# PAYL0004_PC_Microcontroller_IOIfaces.net
KiCad netlist of a schematic drawn in Altium Designer
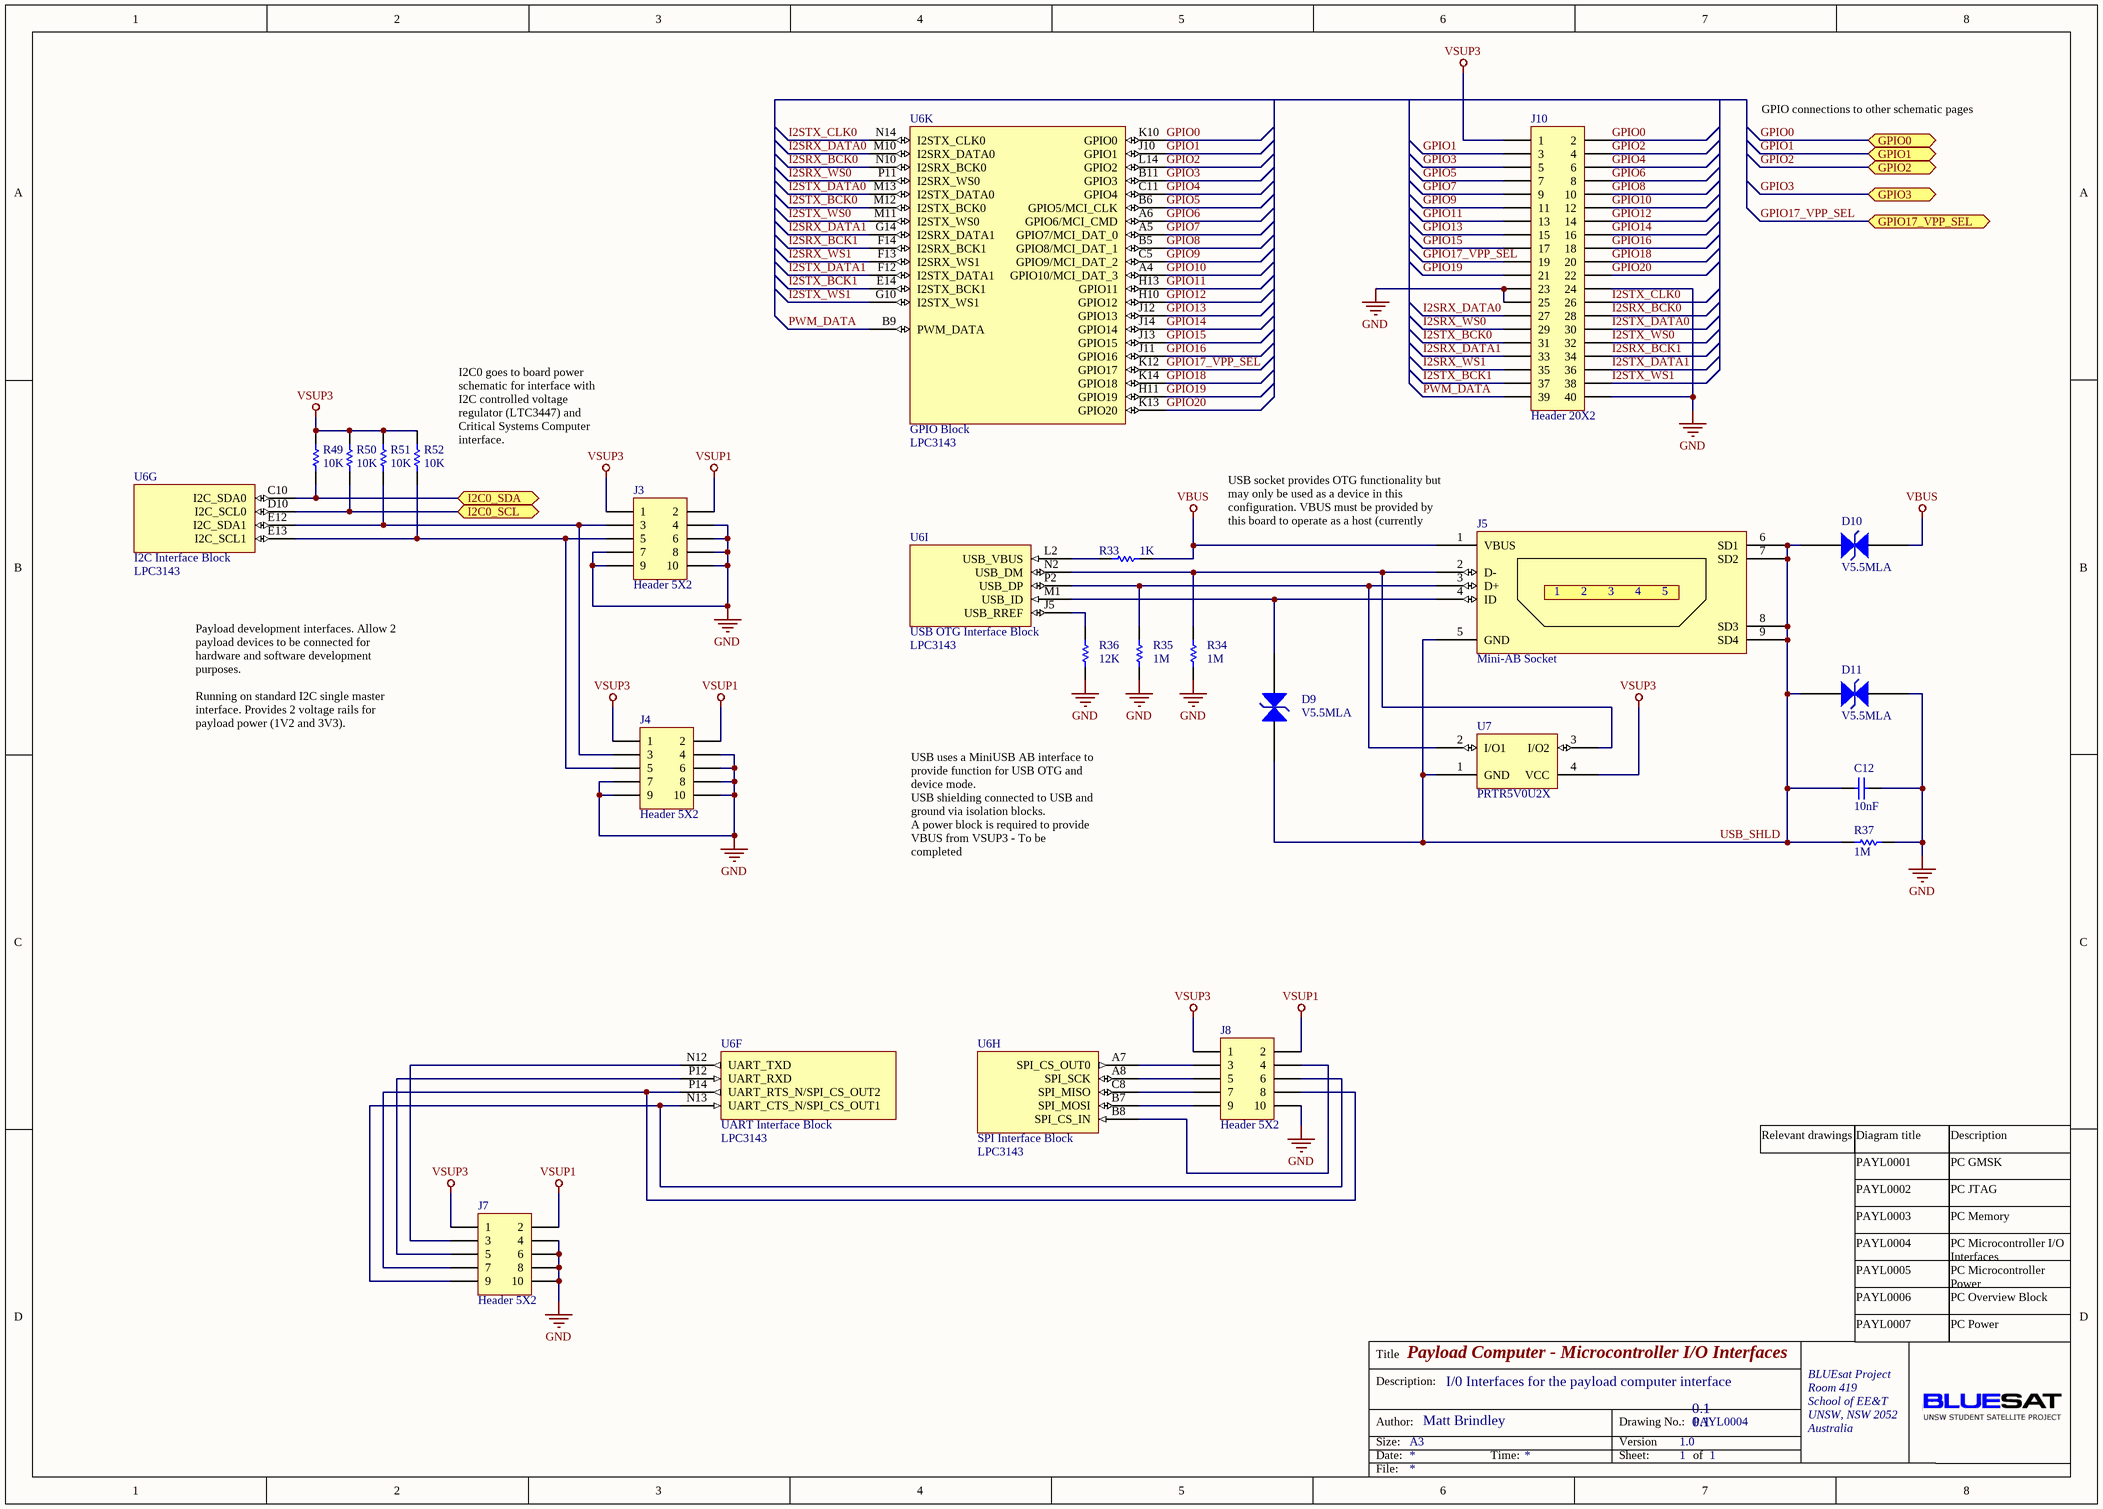
[diagram p0: PAYL0004_PC_Microcontroller_IOIfaces.SchDoc]

(export (version "E")
  (design (tool "Eeschema 10.0.6"))
  (components
    (comp (ref "C12")
      (value "10nF")
      (footprint "C0805")
      (description "Capacitor (Semiconductor SIM Model)")
      (fields (field (name "Comment") "Cap Semi") (field (name "PUBLISHER") "Altium Limited"))
      (libsource (lib "Miscellaneous Devices") (part "Cap Semi"))
    )
    (comp (ref "D9")
      (value "V5.5MLA")
      (footprint "MLA-1206")
      (description "Multilayer varistor - Transient voltage protection device")
      (fields (field (name "PUBLISHER") "Altium Limited"))
      (libsource (lib "PC_Components") (part "V5.5MLA0603"))
    )
    (comp (ref "D10")
      (value "V5.5MLA")
      (footprint "MLA-1206")
      (description "Multilayer varistor - Transient voltage protection device")
      (fields (field (name "PUBLISHER") "Altium Limited"))
      (libsource (lib "PC_Components") (part "V5.5MLA0603"))
    )
    (comp (ref "D11")
      (value "V5.5MLA")
      (footprint "MLA-1206")
      (description "Multilayer varistor - Transient voltage protection device")
      (fields (field (name "PUBLISHER") "Altium Limited"))
      (libsource (lib "PC_Components") (part "V5.5MLA0603"))
    )
    (comp (ref "J3")
      (value "Header 5X2")
      (footprint "HDR2X5")
      (description "Header, 5-Pin, Dual row")
      (fields (field (name "PUBLISHER") "Altium Limited"))
      (libsource (lib "Miscellaneous Connectors") (part "Header 5X2"))
    )
    (comp (ref "J4")
      (value "Header 5X2")
      (footprint "HDR2X5")
      (description "Header, 5-Pin, Dual row")
      (fields (field (name "PUBLISHER") "Altium Limited"))
      (libsource (lib "Miscellaneous Connectors") (part "Header 5X2"))
    )
    (comp (ref "J5")
      (value "Mini-AB Socket")
      (footprint "miniUSB-AB")
      (description "MiniUSB AB type socket")
      (fields (field (name "PUBLISHER") "Altium Limited"))
      (libsource (lib "PC_Components") (part "miniUSB-AB"))
    )
    (comp (ref "J7")
      (value "Header 5X2")
      (footprint "HDR2X5")
      (description "Header, 5-Pin, Dual row")
      (fields (field (name "PUBLISHER") "Altium Limited"))
      (libsource (lib "Miscellaneous Connectors") (part "Header 5X2"))
    )
    (comp (ref "J8")
      (value "Header 5X2")
      (footprint "HDR2X5")
      (description "Header, 5-Pin, Dual row")
      (fields (field (name "PUBLISHER") "Altium Limited"))
      (libsource (lib "Miscellaneous Connectors") (part "Header 5X2"))
    )
    (comp (ref "J10")
      (value "Header 20X2")
      (footprint "HDR2X20")
      (description "Header, 20-Pin, Dual row")
      (fields (field (name "PUBLISHER") "Altium Limited"))
      (libsource (lib "Miscellaneous Connectors") (part "Header 20X2"))
    )
    (comp (ref "R33")
      (value "1K")
      (footprint "6-0805_L")
      (description "Semiconductor Resistor")
      (fields (field (name "Comment") "Res Semi") (field (name "PUBLISHER") "Altium Limited"))
      (libsource (lib "Miscellaneous Devices") (part "Res Semi"))
    )
    (comp (ref "R34")
      (value "1M")
      (footprint "6-0805_L")
      (description "Semiconductor Resistor")
      (fields (field (name "Comment") "Res Semi") (field (name "PUBLISHER") "Altium Limited"))
      (libsource (lib "Miscellaneous Devices") (part "Res Semi"))
    )
    (comp (ref "R35")
      (value "1M")
      (footprint "6-0805_L")
      (description "Semiconductor Resistor")
      (fields (field (name "Comment") "Res Semi") (field (name "PUBLISHER") "Altium Limited"))
      (libsource (lib "Miscellaneous Devices") (part "Res Semi"))
    )
    (comp (ref "R36")
      (value "12K")
      (footprint "6-0805_L")
      (description "Semiconductor Resistor")
      (fields (field (name "Comment") "Res Semi") (field (name "PUBLISHER") "Altium Limited"))
      (libsource (lib "Miscellaneous Devices") (part "Res Semi"))
    )
    (comp (ref "R37")
      (value "1M")
      (footprint "6-0805_L")
      (description "Semiconductor Resistor")
      (fields (field (name "Comment") "Res Semi") (field (name "PUBLISHER") "Altium Limited"))
      (libsource (lib "Miscellaneous Devices") (part "Res Semi"))
    )
    (comp (ref "R49")
      (value "10K")
      (footprint "6-0805_L")
      (description "Semiconductor Resistor")
      (fields (field (name "Comment") "Res Semi") (field (name "PUBLISHER") "Altium Limited"))
      (libsource (lib "Miscellaneous Devices") (part "Res Semi"))
    )
    (comp (ref "R50")
      (value "10K")
      (footprint "6-0805_L")
      (description "Semiconductor Resistor")
      (fields (field (name "Comment") "Res Semi") (field (name "PUBLISHER") "Altium Limited"))
      (libsource (lib "Miscellaneous Devices") (part "Res Semi"))
    )
    (comp (ref "R51")
      (value "10K")
      (footprint "6-0805_L")
      (description "Semiconductor Resistor")
      (fields (field (name "Comment") "Res Semi") (field (name "PUBLISHER") "Altium Limited"))
      (libsource (lib "Miscellaneous Devices") (part "Res Semi"))
    )
    (comp (ref "R52")
      (value "10K")
      (footprint "6-0805_L")
      (description "Semiconductor Resistor")
      (fields (field (name "Comment") "Res Semi") (field (name "PUBLISHER") "Altium Limited"))
      (libsource (lib "Miscellaneous Devices") (part "Res Semi"))
    )
    (comp (ref "U6")
      (value "LPC3143")
      (footprint "PC_Footprints:BGA180C80P14X14_1200X1200X120")
      (description "NXP ARM9 based microcontroller")
      (fields (field (name "PUBLISHER") "BLUEsat Project"))
      (libsource (lib "PC_Components") (part "LPC3143"))
    )
    (comp (ref "U7")
      (value "PRTR5V0U2X")
      (footprint "SOT190P230X110-4N")
      (description "Electrostatic discharge protection diode IC - NXP")
      (fields (field (name "PUBLISHER") "Altium Limited"))
      (libsource (lib "PC_Components") (part "PRTR5V0U2X"))
    )
  )
  (nets
    (net (code "1") (name "/GPIO0") (class "Default")
      (node (ref "J10") (pin "2") (pinfunction "2_2") (pintype "passive"))
      (node (ref "U6") (pin "K10") (pinfunction "GPIO0_K10") (pintype "bidirectional"))
    )
    (net (code "2") (name "/GPIO1") (class "Default")
      (node (ref "J10") (pin "3") (pinfunction "3_3") (pintype "passive"))
      (node (ref "U6") (pin "J10") (pinfunction "GPIO1_J10") (pintype "bidirectional"))
    )
    (net (code "3") (name "/GPIO2") (class "Default")
      (node (ref "J10") (pin "4") (pinfunction "4_4") (pintype "passive"))
      (node (ref "U6") (pin "L14") (pinfunction "GPIO2_L14") (pintype "bidirectional"))
    )
    (net (code "4") (name "/GPIO3") (class "Default")
      (node (ref "J10") (pin "5") (pinfunction "5_5") (pintype "passive"))
      (node (ref "U6") (pin "B11") (pinfunction "GPIO3_B11") (pintype "bidirectional"))
    )
    (net (code "5") (name "/GPIO4") (class "Default")
      (node (ref "J10") (pin "6") (pinfunction "6_6") (pintype "passive"))
      (node (ref "U6") (pin "C11") (pinfunction "GPIO4_C11") (pintype "bidirectional"))
    )
    (net (code "6") (name "/GPIO5") (class "Default")
      (node (ref "J10") (pin "7") (pinfunction "7_7") (pintype "passive"))
      (node (ref "U6") (pin "B6") (pinfunction "GPIO5/MCI_CLK_B6") (pintype "bidirectional"))
    )
    (net (code "7") (name "/GPIO6") (class "Default")
      (node (ref "J10") (pin "8") (pinfunction "8_8") (pintype "passive"))
      (node (ref "U6") (pin "A6") (pinfunction "GPIO6/MCI_CMD_A6") (pintype "bidirectional"))
    )
    (net (code "8") (name "/GPIO7") (class "Default")
      (node (ref "J10") (pin "9") (pinfunction "9_9") (pintype "passive"))
      (node (ref "U6") (pin "A5") (pinfunction "GPIO7/MCI_DAT_0_A5") (pintype "bidirectional"))
    )
    (net (code "9") (name "/GPIO8") (class "Default")
      (node (ref "J10") (pin "10") (pinfunction "10_10") (pintype "passive"))
      (node (ref "U6") (pin "B5") (pinfunction "GPIO8/MCI_DAT_1_B5") (pintype "bidirectional"))
    )
    (net (code "10") (name "/GPIO9") (class "Default")
      (node (ref "J10") (pin "11") (pinfunction "11_11") (pintype "passive"))
      (node (ref "U6") (pin "C5") (pinfunction "GPIO9/MCI_DAT_2_C5") (pintype "bidirectional"))
    )
    (net (code "11") (name "/GPIO10") (class "Default")
      (node (ref "J10") (pin "12") (pinfunction "12_12") (pintype "passive"))
      (node (ref "U6") (pin "A4") (pinfunction "GPIO10/MCI_DAT_3_A4") (pintype "bidirectional"))
    )
    (net (code "12") (name "/GPIO11") (class "Default")
      (node (ref "J10") (pin "13") (pinfunction "13_13") (pintype "passive"))
      (node (ref "U6") (pin "H13") (pinfunction "GPIO11_H13") (pintype "bidirectional"))
    )
    (net (code "13") (name "/GPIO12") (class "Default")
      (node (ref "J10") (pin "14") (pinfunction "14_14") (pintype "passive"))
      (node (ref "U6") (pin "H10") (pinfunction "GPIO12_H10") (pintype "bidirectional"))
    )
    (net (code "14") (name "/GPIO13") (class "Default")
      (node (ref "J10") (pin "15") (pinfunction "15_15") (pintype "passive"))
      (node (ref "U6") (pin "J12") (pinfunction "GPIO13_J12") (pintype "bidirectional"))
    )
    (net (code "15") (name "/GPIO14") (class "Default")
      (node (ref "J10") (pin "16") (pinfunction "16_16") (pintype "passive"))
      (node (ref "U6") (pin "J14") (pinfunction "GPIO14_J14") (pintype "bidirectional"))
    )
    (net (code "16") (name "/GPIO15") (class "Default")
      (node (ref "J10") (pin "17") (pinfunction "17_17") (pintype "passive"))
      (node (ref "U6") (pin "J13") (pinfunction "GPIO15_J13") (pintype "bidirectional"))
    )
    (net (code "17") (name "/GPIO16") (class "Default")
      (node (ref "J10") (pin "18") (pinfunction "18_18") (pintype "passive"))
      (node (ref "U6") (pin "J11") (pinfunction "GPIO16_J11") (pintype "bidirectional"))
    )
    (net (code "18") (name "/GPIO17_VPP_SEL") (class "Default")
      (node (ref "J10") (pin "19") (pinfunction "19_19") (pintype "passive"))
      (node (ref "U6") (pin "K12") (pinfunction "GPIO17_K12") (pintype "bidirectional"))
    )
    (net (code "19") (name "/GPIO18") (class "Default")
      (node (ref "J10") (pin "20") (pinfunction "20_20") (pintype "passive"))
      (node (ref "U6") (pin "K14") (pinfunction "GPIO18_K14") (pintype "bidirectional"))
    )
    (net (code "20") (name "/GPIO19") (class "Default")
      (node (ref "J10") (pin "21") (pinfunction "21_21") (pintype "passive"))
      (node (ref "U6") (pin "H11") (pinfunction "GPIO19_H11") (pintype "bidirectional"))
    )
    (net (code "21") (name "/GPIO20") (class "Default")
      (node (ref "J10") (pin "22") (pinfunction "22_22") (pintype "passive"))
      (node (ref "U6") (pin "K13") (pinfunction "GPIO20_K13") (pintype "bidirectional"))
    )
    (net (code "22") (name "/I2C0_SCL") (class "Default")
      (node (ref "R50") (pin "1") (pinfunction "1_1") (pintype "passive"))
      (node (ref "U6") (pin "D10") (pinfunction "I2C_SCL0_D10") (pintype "bidirectional"))
    )
    (net (code "23") (name "/I2C0_SDA") (class "Default")
      (node (ref "R49") (pin "1") (pinfunction "1_1") (pintype "passive"))
      (node (ref "U6") (pin "C10") (pinfunction "I2C_SDA0_C10") (pintype "bidirectional"))
    )
    (net (code "24") (name "/I2SRX_BCK0") (class "Default")
      (node (ref "J10") (pin "28") (pinfunction "28_28") (pintype "passive"))
      (node (ref "U6") (pin "N10") (pinfunction "I2SRX_BCK0_N10") (pintype "bidirectional"))
    )
    (net (code "25") (name "/I2SRX_BCK1") (class "Default")
      (node (ref "J10") (pin "34") (pinfunction "34_34") (pintype "passive"))
      (node (ref "U6") (pin "F14") (pinfunction "I2SRX_BCK1_F14") (pintype "bidirectional"))
    )
    (net (code "26") (name "/I2SRX_DATA0") (class "Default")
      (node (ref "J10") (pin "27") (pinfunction "27_27") (pintype "passive"))
      (node (ref "U6") (pin "M10") (pinfunction "I2SRX_DATA0_M10") (pintype "bidirectional"))
    )
    (net (code "27") (name "/I2SRX_DATA1") (class "Default")
      (node (ref "J10") (pin "33") (pinfunction "33_33") (pintype "passive"))
      (node (ref "U6") (pin "G14") (pinfunction "I2SRX_DATA1_G14") (pintype "bidirectional"))
    )
    (net (code "28") (name "/I2SRX_WS0") (class "Default")
      (node (ref "J10") (pin "29") (pinfunction "29_29") (pintype "passive"))
      (node (ref "U6") (pin "P11") (pinfunction "I2SRX_WS0_P11") (pintype "bidirectional"))
    )
    (net (code "29") (name "/I2SRX_WS1") (class "Default")
      (node (ref "J10") (pin "35") (pinfunction "35_35") (pintype "passive"))
      (node (ref "U6") (pin "F13") (pinfunction "I2SRX_WS1_F13") (pintype "bidirectional"))
    )
    (net (code "30") (name "/I2STX_BCK0") (class "Default")
      (node (ref "J10") (pin "31") (pinfunction "31_31") (pintype "passive"))
      (node (ref "U6") (pin "M12") (pinfunction "I2STX_BCK0_M12") (pintype "bidirectional"))
    )
    (net (code "31") (name "/I2STX_BCK1") (class "Default")
      (node (ref "J10") (pin "37") (pinfunction "37_37") (pintype "passive"))
      (node (ref "U6") (pin "E14") (pinfunction "I2STX_BCK1_E14") (pintype "bidirectional"))
    )
    (net (code "32") (name "/I2STX_CLK0") (class "Default")
      (node (ref "J10") (pin "26") (pinfunction "26_26") (pintype "passive"))
      (node (ref "U6") (pin "N14") (pinfunction "I2STX_CLK0_N14") (pintype "bidirectional"))
    )
    (net (code "33") (name "/I2STX_DATA0") (class "Default")
      (node (ref "J10") (pin "30") (pinfunction "30_30") (pintype "passive"))
      (node (ref "U6") (pin "M13") (pinfunction "I2STX_DATA0_M13") (pintype "bidirectional"))
    )
    (net (code "34") (name "/I2STX_DATA1") (class "Default")
      (node (ref "J10") (pin "36") (pinfunction "36_36") (pintype "passive"))
      (node (ref "U6") (pin "F12") (pinfunction "I2STX_DATA1_F12") (pintype "bidirectional"))
    )
    (net (code "35") (name "/I2STX_WS0") (class "Default")
      (node (ref "J10") (pin "32") (pinfunction "32_32") (pintype "passive"))
      (node (ref "U6") (pin "M11") (pinfunction "I2STX_WS0_M11") (pintype "bidirectional"))
    )
    (net (code "36") (name "/I2STX_WS1") (class "Default")
      (node (ref "J10") (pin "38") (pinfunction "38_38") (pintype "passive"))
      (node (ref "U6") (pin "G10") (pinfunction "I2STX_WS1_G10") (pintype "bidirectional"))
    )
    (net (code "37") (name "/PWM_DATA") (class "Default")
      (node (ref "J10") (pin "39") (pinfunction "39_39") (pintype "passive"))
      (node (ref "U6") (pin "B9") (pinfunction "PWM_DATA_B9") (pintype "bidirectional"))
    )
    (net (code "38") (name "/USB_SHLD") (class "Default")
      (node (ref "C12") (pin "2") (pinfunction "2_2") (pintype "passive"))
      (node (ref "D10") (pin "2") (pinfunction "2_2") (pintype "passive"))
      (node (ref "D11") (pin "2") (pinfunction "2_2") (pintype "passive"))
      (node (ref "D9") (pin "1") (pinfunction "1_1") (pintype "passive"))
      (node (ref "J5") (pin "5") (pinfunction "GND_5") (pintype "power_in"))
      (node (ref "J5") (pin "6") (pinfunction "SD1_6") (pintype "passive"))
      (node (ref "J5") (pin "7") (pinfunction "SD2_7") (pintype "passive"))
      (node (ref "J5") (pin "8") (pinfunction "SD3_8") (pintype "passive"))
      (node (ref "J5") (pin "9") (pinfunction "SD4_9") (pintype "passive"))
      (node (ref "R37") (pin "2") (pinfunction "2_2") (pintype "passive"))
      (node (ref "U7") (pin "1") (pinfunction "GND_1") (pintype "power_in"))
    )
    (net (code "39") (name "GND") (class "Default")
      (node (ref "C12") (pin "1") (pinfunction "1_1") (pintype "passive"))
      (node (ref "D11") (pin "1") (pinfunction "1_1") (pintype "passive"))
      (node (ref "J10") (pin "23") (pinfunction "23_23") (pintype "passive"))
      (node (ref "J10") (pin "24") (pinfunction "24_24") (pintype "passive"))
      (node (ref "J10") (pin "25") (pinfunction "25_25") (pintype "passive"))
      (node (ref "J10") (pin "40") (pinfunction "40_40") (pintype "passive"))
      (node (ref "J3") (pin "10") (pinfunction "10_10") (pintype "passive"))
      (node (ref "J3") (pin "4") (pinfunction "4_4") (pintype "passive"))
      (node (ref "J3") (pin "6") (pinfunction "6_6") (pintype "passive"))
      (node (ref "J3") (pin "7") (pinfunction "7_7") (pintype "passive"))
      (node (ref "J3") (pin "8") (pinfunction "8_8") (pintype "passive"))
      (node (ref "J3") (pin "9") (pinfunction "9_9") (pintype "passive"))
      (node (ref "J4") (pin "10") (pinfunction "10_10") (pintype "passive"))
      (node (ref "J4") (pin "4") (pinfunction "4_4") (pintype "passive"))
      (node (ref "J4") (pin "6") (pinfunction "6_6") (pintype "passive"))
      (node (ref "J4") (pin "7") (pinfunction "7_7") (pintype "passive"))
      (node (ref "J4") (pin "8") (pinfunction "8_8") (pintype "passive"))
      (node (ref "J4") (pin "9") (pinfunction "9_9") (pintype "passive"))
      (node (ref "J7") (pin "10") (pinfunction "10_10") (pintype "passive"))
      (node (ref "J7") (pin "4") (pinfunction "4_4") (pintype "passive"))
      (node (ref "J7") (pin "6") (pinfunction "6_6") (pintype "passive"))
      (node (ref "J7") (pin "8") (pinfunction "8_8") (pintype "passive"))
      (node (ref "J8") (pin "10") (pinfunction "10_10") (pintype "passive"))
      (node (ref "R34") (pin "1") (pinfunction "1_1") (pintype "passive"))
      (node (ref "R35") (pin "1") (pinfunction "1_1") (pintype "passive"))
      (node (ref "R36") (pin "1") (pinfunction "1_1") (pintype "passive"))
      (node (ref "R37") (pin "1") (pinfunction "1_1") (pintype "passive"))
    )
    (net (code "40") (name "Net-(J5-D+)") (class "Default")
      (node (ref "J5") (pin "3") (pinfunction "D+_3") (pintype "bidirectional"))
      (node (ref "R35") (pin "2") (pinfunction "2_2") (pintype "passive"))
      (node (ref "U6") (pin "P2") (pinfunction "USB_DP_P2") (pintype "bidirectional"))
      (node (ref "U7") (pin "2") (pinfunction "I/O1_2") (pintype "bidirectional"))
    )
    (net (code "41") (name "Net-(J5-D-)") (class "Default")
      (node (ref "J5") (pin "2") (pinfunction "D-_2") (pintype "bidirectional"))
      (node (ref "R34") (pin "2") (pinfunction "2_2") (pintype "passive"))
      (node (ref "U6") (pin "N2") (pinfunction "USB_DM_N2") (pintype "bidirectional"))
      (node (ref "U7") (pin "3") (pinfunction "I/O2_3") (pintype "bidirectional"))
    )
    (net (code "42") (name "Net-(J5-ID)") (class "Default")
      (node (ref "D9") (pin "2") (pinfunction "2_2") (pintype "passive"))
      (node (ref "J5") (pin "4") (pinfunction "ID_4") (pintype "bidirectional"))
      (node (ref "U6") (pin "M1") (pinfunction "USB_ID_M1") (pintype "input"))
    )
    (net (code "43") (name "Net-(U6F-UART_CTS_N{slash}SPI_CS_OUT1)") (class "Default")
      (node (ref "J7") (pin "9") (pinfunction "9_9") (pintype "passive"))
      (node (ref "J8") (pin "6") (pinfunction "6_6") (pintype "passive"))
      (node (ref "U6") (pin "N13") (pinfunction "UART_CTS_N/SPI_CS_OUT1_N13") (pintype "input"))
    )
    (net (code "44") (name "Net-(U6F-UART_RTS_N{slash}SPI_CS_OUT2)") (class "Default")
      (node (ref "J7") (pin "7") (pinfunction "7_7") (pintype "passive"))
      (node (ref "J8") (pin "8") (pinfunction "8_8") (pintype "passive"))
      (node (ref "U6") (pin "P14") (pinfunction "UART_RTS_N/SPI_CS_OUT2_P14") (pintype "output"))
    )
    (net (code "45") (name "Net-(U6F-UART_RXD)") (class "Default")
      (node (ref "J7") (pin "5") (pinfunction "5_5") (pintype "passive"))
      (node (ref "U6") (pin "P12") (pinfunction "UART_RXD_P12") (pintype "input"))
    )
    (net (code "46") (name "Net-(U6F-UART_TXD)") (class "Default")
      (node (ref "J7") (pin "3") (pinfunction "3_3") (pintype "passive"))
      (node (ref "U6") (pin "N12") (pinfunction "UART_TXD_N12") (pintype "output"))
    )
    (net (code "47") (name "Net-(U6G-I2C_SCL1)") (class "Default")
      (node (ref "J3") (pin "5") (pinfunction "5_5") (pintype "passive"))
      (node (ref "J4") (pin "5") (pinfunction "5_5") (pintype "passive"))
      (node (ref "R52") (pin "1") (pinfunction "1_1") (pintype "passive"))
      (node (ref "U6") (pin "E13") (pinfunction "I2C_SCL1_E13") (pintype "bidirectional"))
    )
    (net (code "48") (name "Net-(U6G-I2C_SDA1)") (class "Default")
      (node (ref "J3") (pin "3") (pinfunction "3_3") (pintype "passive"))
      (node (ref "J4") (pin "3") (pinfunction "3_3") (pintype "passive"))
      (node (ref "R51") (pin "1") (pinfunction "1_1") (pintype "passive"))
      (node (ref "U6") (pin "E12") (pinfunction "I2C_SDA1_E12") (pintype "bidirectional"))
    )
    (net (code "49") (name "Net-(U6H-SPI_CS_IN)") (class "Default")
      (node (ref "J8") (pin "4") (pinfunction "4_4") (pintype "passive"))
      (node (ref "U6") (pin "B8") (pinfunction "SPI_CS_IN_B8") (pintype "input"))
    )
    (net (code "50") (name "Net-(U6H-SPI_CS_OUT0)") (class "Default")
      (node (ref "J8") (pin "3") (pinfunction "3_3") (pintype "passive"))
      (node (ref "U6") (pin "A7") (pinfunction "SPI_CS_OUT0_A7") (pintype "output"))
    )
    (net (code "51") (name "Net-(U6H-SPI_MISO)") (class "Default")
      (node (ref "J8") (pin "7") (pinfunction "7_7") (pintype "passive"))
      (node (ref "U6") (pin "C8") (pinfunction "SPI_MISO_C8") (pintype "bidirectional"))
    )
    (net (code "52") (name "Net-(U6H-SPI_MOSI)") (class "Default")
      (node (ref "J8") (pin "9") (pinfunction "9_9") (pintype "passive"))
      (node (ref "U6") (pin "B7") (pinfunction "SPI_MOSI_B7") (pintype "bidirectional"))
    )
    (net (code "53") (name "Net-(U6H-SPI_SCK)") (class "Default")
      (node (ref "J8") (pin "5") (pinfunction "5_5") (pintype "passive"))
      (node (ref "U6") (pin "A8") (pinfunction "SPI_SCK_A8") (pintype "bidirectional"))
    )
    (net (code "54") (name "Net-(U6I-USB_RREF)") (class "Default")
      (node (ref "R36") (pin "2") (pinfunction "2_2") (pintype "passive"))
      (node (ref "U6") (pin "J5") (pinfunction "USB_RREF_J5") (pintype "bidirectional"))
    )
    (net (code "55") (name "Net-(U6I-USB_VBUS)") (class "Default")
      (node (ref "R33") (pin "1") (pinfunction "1_1") (pintype "passive"))
      (node (ref "U6") (pin "L2") (pinfunction "USB_VBUS_L2") (pintype "input"))
    )
    (net (code "56") (name "VBUS") (class "Default")
      (node (ref "D10") (pin "1") (pinfunction "1_1") (pintype "passive"))
      (node (ref "J5") (pin "1") (pinfunction "VBUS_1") (pintype "power_in"))
      (node (ref "R33") (pin "2") (pinfunction "2_2") (pintype "passive"))
    )
    (net (code "57") (name "VSUP1") (class "Default")
      (node (ref "J3") (pin "2") (pinfunction "2_2") (pintype "passive"))
      (node (ref "J4") (pin "2") (pinfunction "2_2") (pintype "passive"))
      (node (ref "J7") (pin "2") (pinfunction "2_2") (pintype "passive"))
      (node (ref "J8") (pin "2") (pinfunction "2_2") (pintype "passive"))
    )
    (net (code "58") (name "VSUP3") (class "Default")
      (node (ref "J10") (pin "1") (pinfunction "1_1") (pintype "passive"))
      (node (ref "J3") (pin "1") (pinfunction "1_1") (pintype "passive"))
      (node (ref "J4") (pin "1") (pinfunction "1_1") (pintype "passive"))
      (node (ref "J7") (pin "1") (pinfunction "1_1") (pintype "passive"))
      (node (ref "J8") (pin "1") (pinfunction "1_1") (pintype "passive"))
      (node (ref "R49") (pin "2") (pinfunction "2_2") (pintype "passive"))
      (node (ref "R50") (pin "2") (pinfunction "2_2") (pintype "passive"))
      (node (ref "R51") (pin "2") (pinfunction "2_2") (pintype "passive"))
      (node (ref "R52") (pin "2") (pinfunction "2_2") (pintype "passive"))
      (node (ref "U7") (pin "4") (pinfunction "VCC_4") (pintype "power_in"))
    )
  )
)
